# Bordnetzwandler.net
KiCad netlist of a schematic drawn in EAGLE
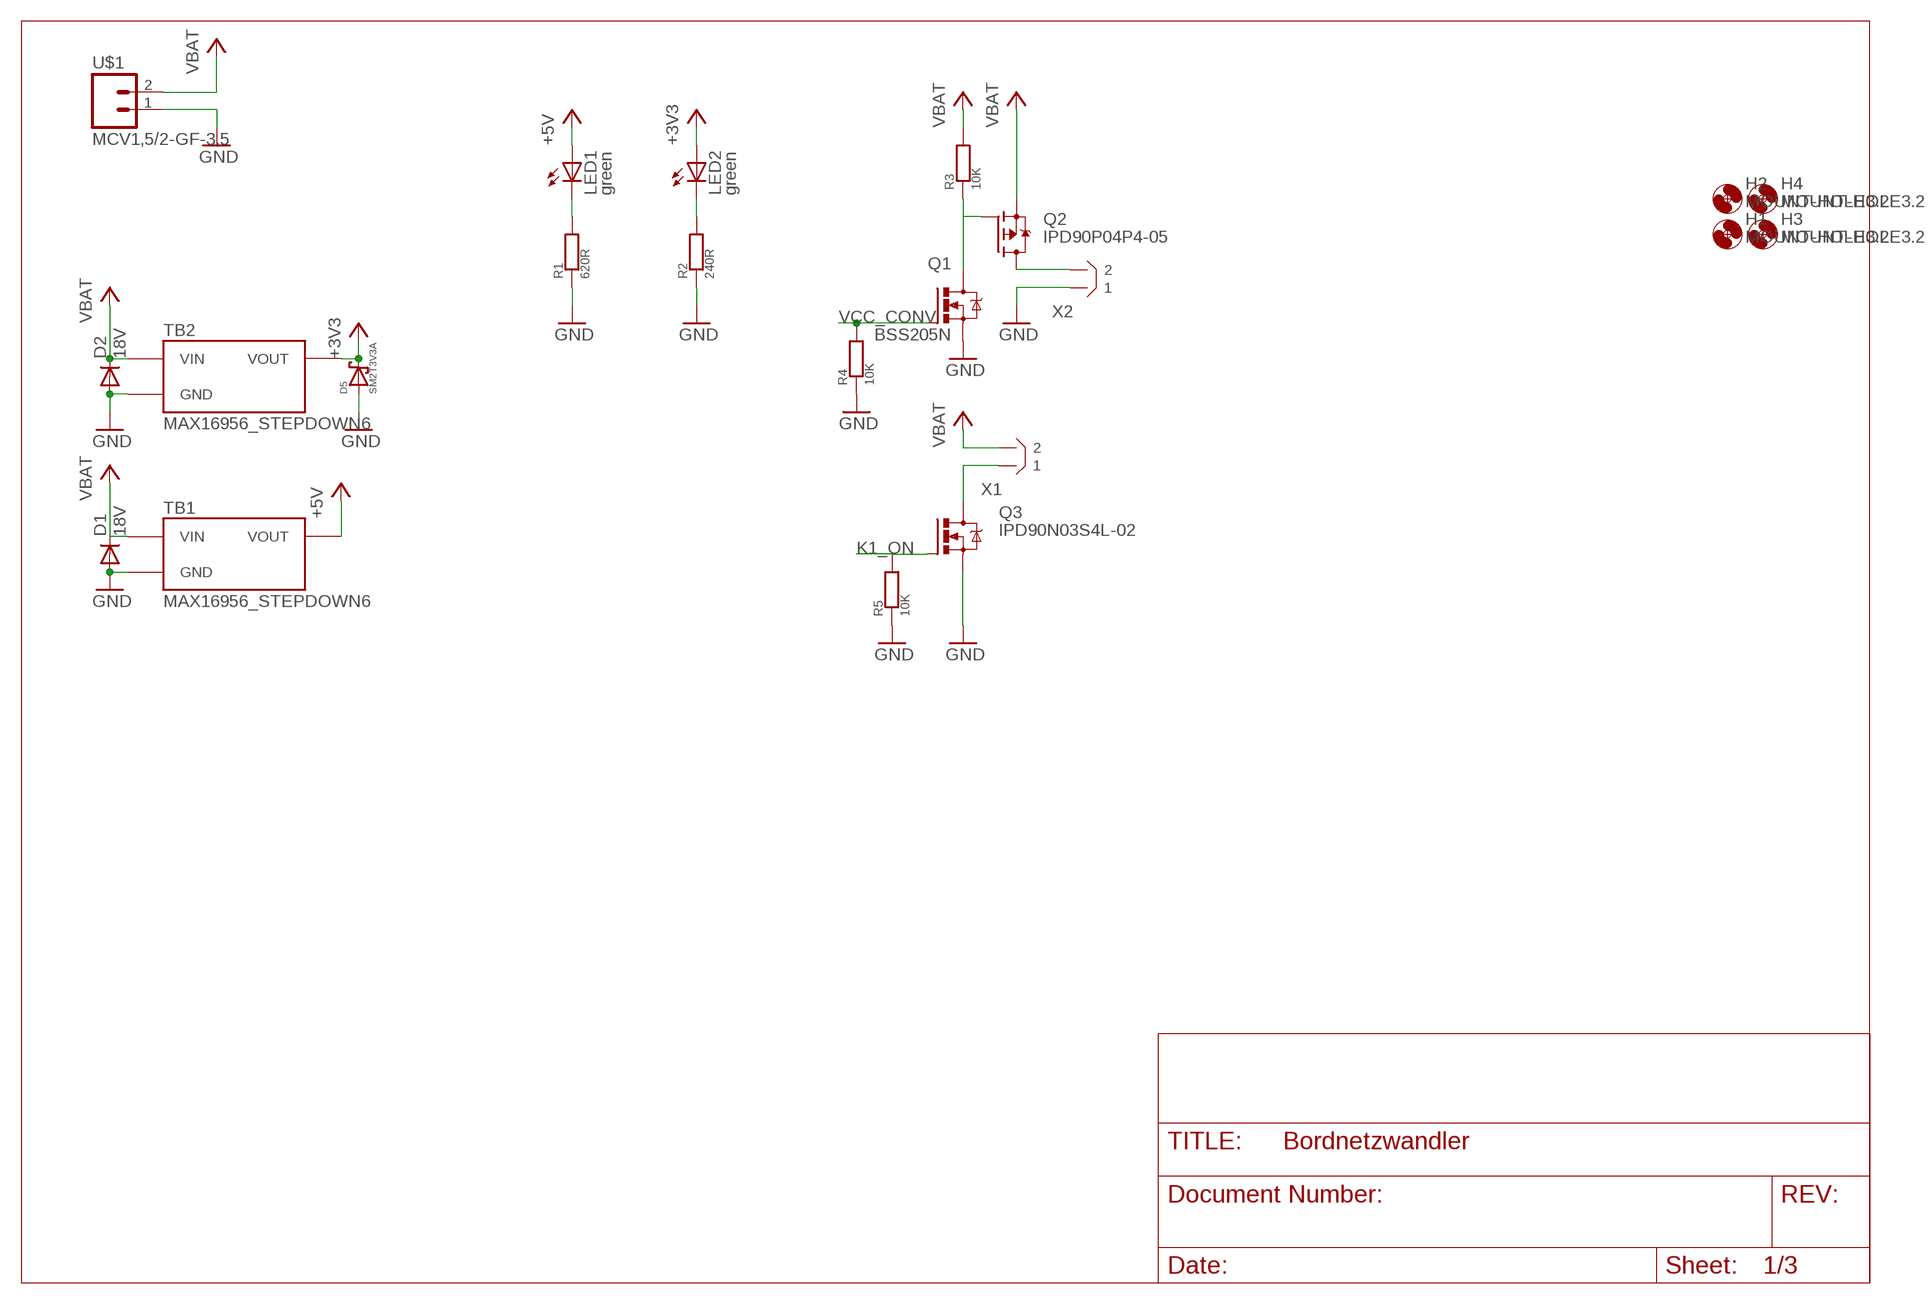
[diagram p0: schematic, sheet 1]
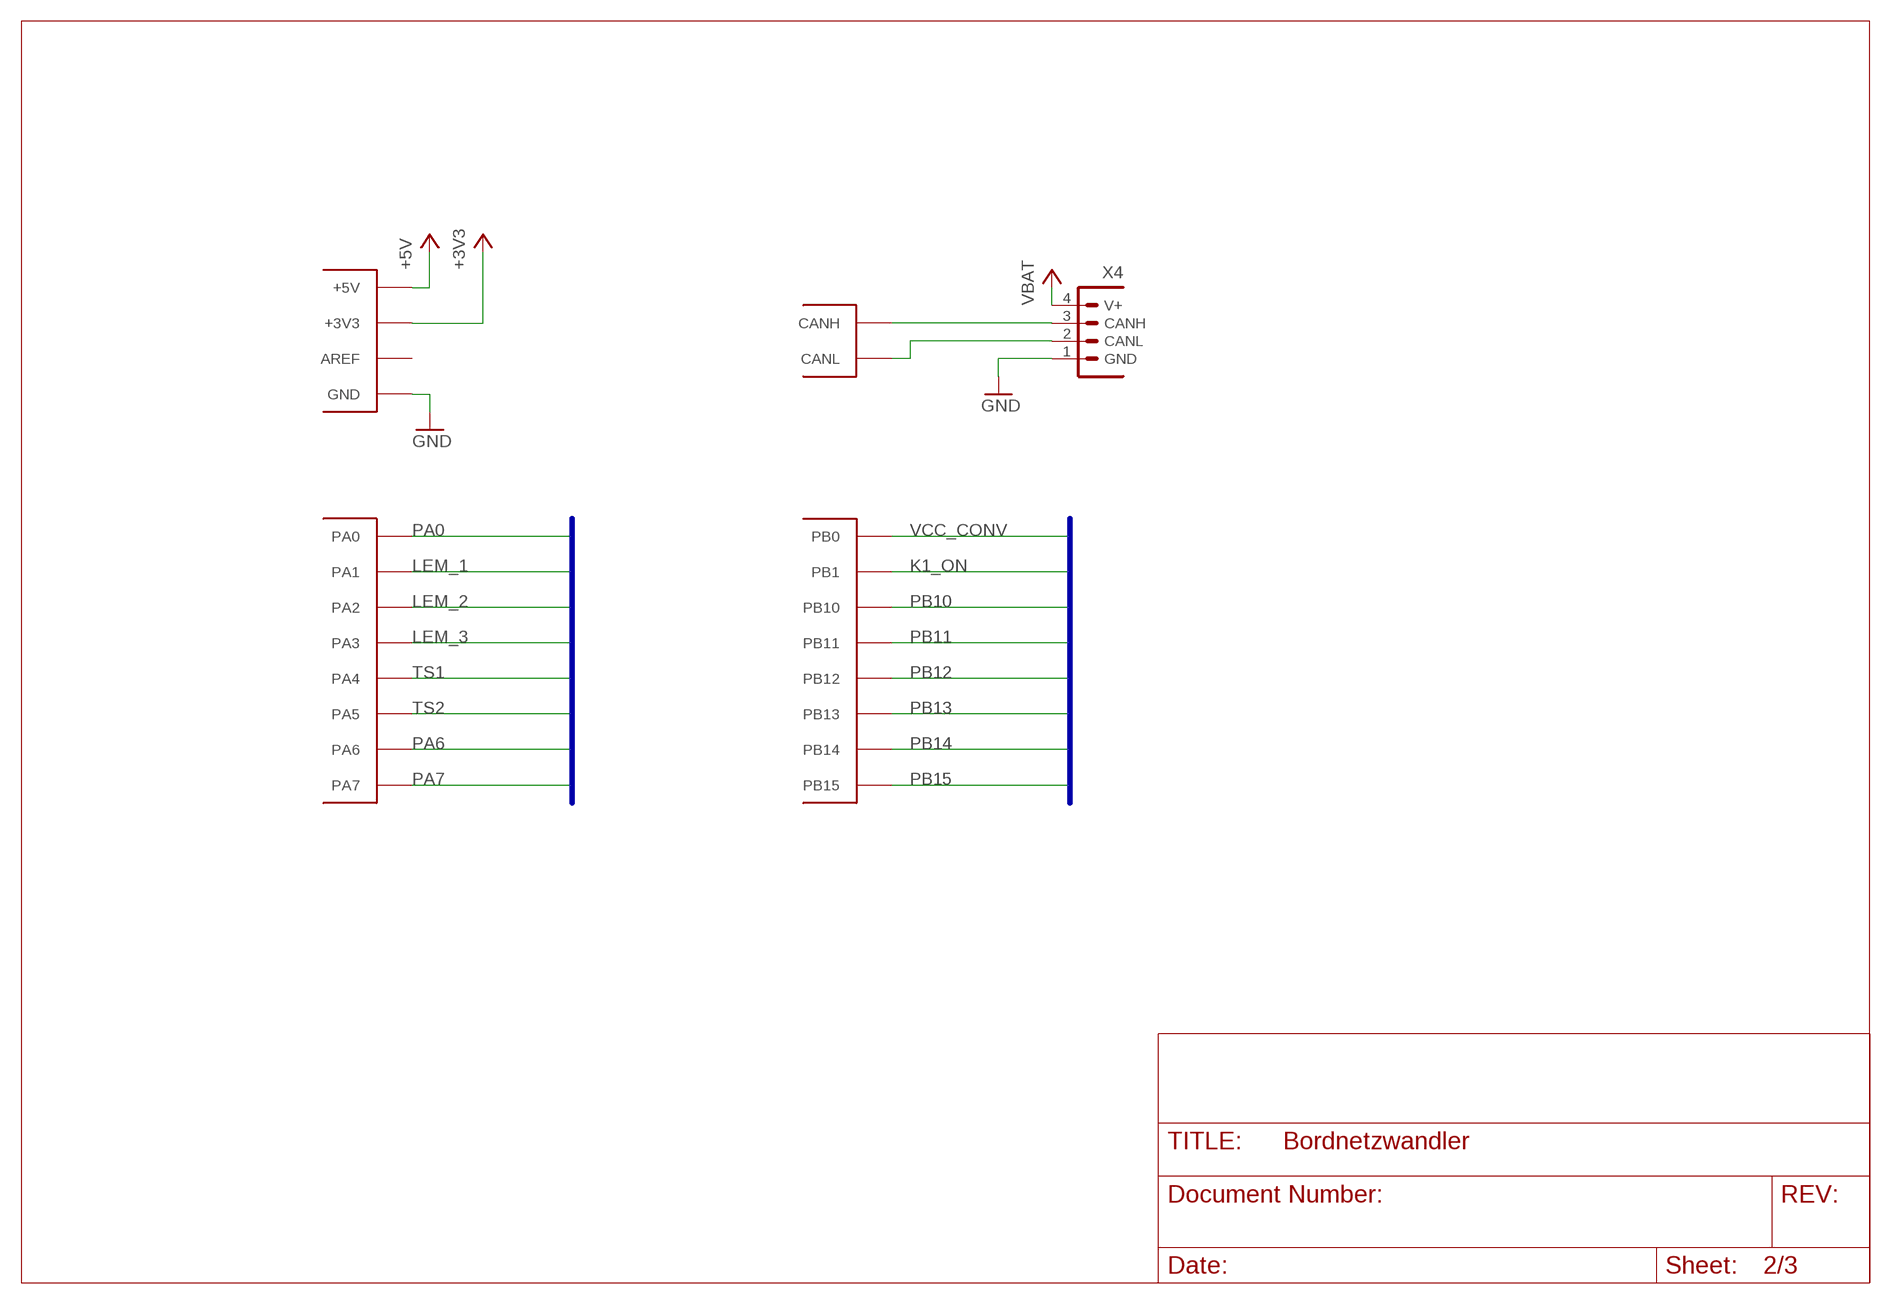
[diagram p1: schematic, sheet 2]
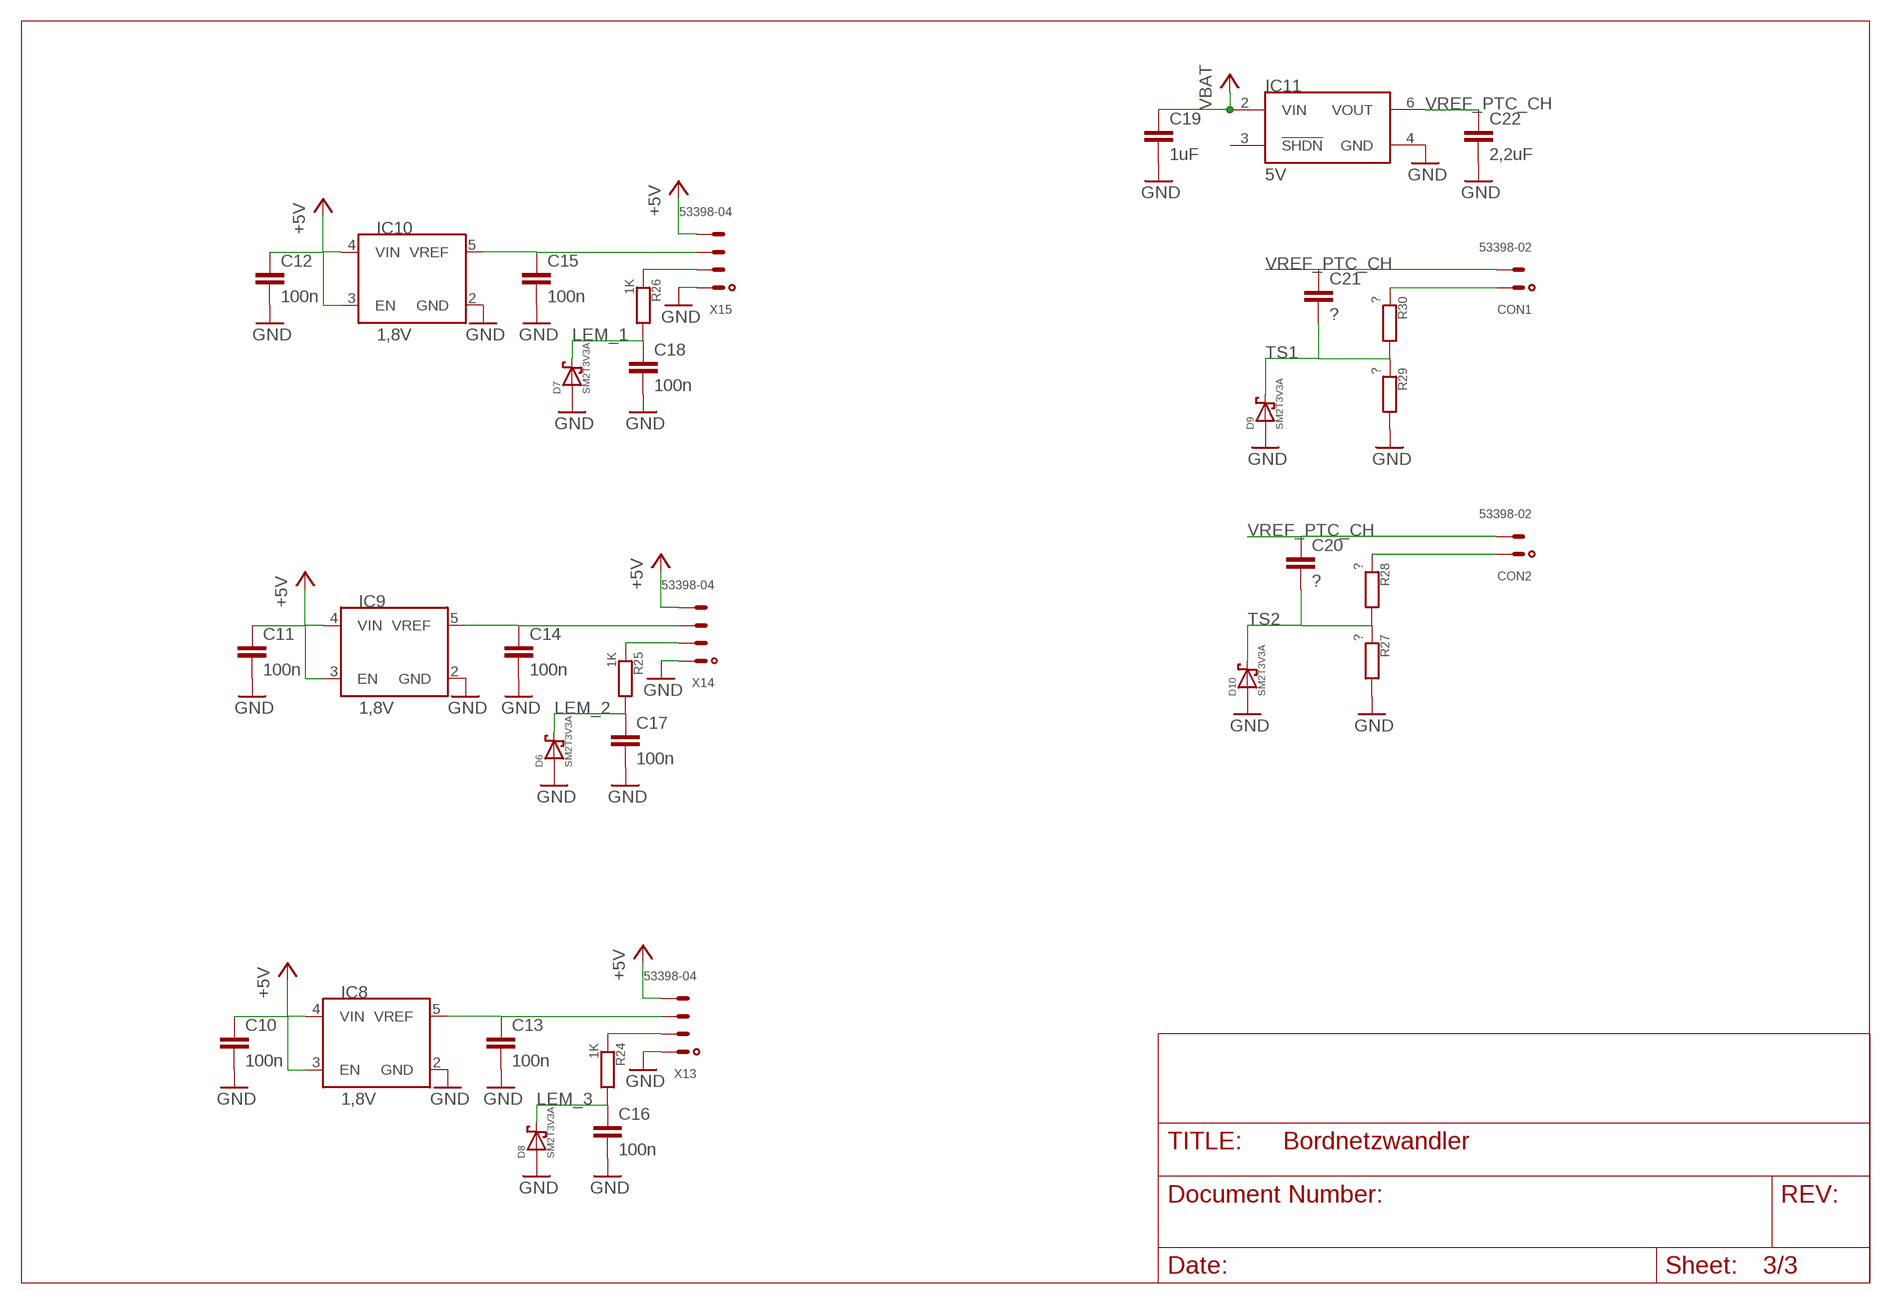
[diagram p2: schematic, sheet 3]

(export (version "E")
  (design (tool "Eeschema 10.0.6"))
  (components
    (comp (ref "CANIO_1")
      (value "STM32F103XX_CAN-IO-EXPANDER")
      (footprint "eagle-import:STM32F103XX_CANIO-EXPANDER")
      (libsource (lib "eagle-import") (part "STM32F103XX_CAN-IO-EXPANDER"))
    )
    (comp (ref "X4")
      (value "CIOC_4-1-FV-A_CAN-BELEGUNG")
      (footprint "eagle-import:CIOC_4-1-FV")
      (libsource (lib "eagle-import") (part "CIOC_4-1-FV-A_CAN-BELEGUNG"))
    )
    (comp (ref "C10")
      (value "100n")
      (footprint "eagle-import:C0805")
      (libsource (lib "eagle-import") (part "C-EUC0805"))
    )
    (comp (ref "C11")
      (value "100n")
      (footprint "eagle-import:C0805")
      (libsource (lib "eagle-import") (part "C-EUC0805"))
    )
    (comp (ref "C12")
      (value "100n")
      (footprint "eagle-import:C0805")
      (libsource (lib "eagle-import") (part "C-EUC0805"))
    )
    (comp (ref "C13")
      (value "100n")
      (footprint "eagle-import:C0805")
      (libsource (lib "eagle-import") (part "C-EUC0805"))
    )
    (comp (ref "C14")
      (value "100n")
      (footprint "eagle-import:C0805")
      (libsource (lib "eagle-import") (part "C-EUC0805"))
    )
    (comp (ref "C15")
      (value "100n")
      (footprint "eagle-import:C0805")
      (libsource (lib "eagle-import") (part "C-EUC0805"))
    )
    (comp (ref "C16")
      (value "100n")
      (footprint "eagle-import:C0805")
      (libsource (lib "eagle-import") (part "C-EUC0805"))
    )
    (comp (ref "C17")
      (value "100n")
      (footprint "eagle-import:C0805")
      (libsource (lib "eagle-import") (part "C-EUC0805"))
    )
    (comp (ref "C18")
      (value "100n")
      (footprint "eagle-import:C0805")
      (libsource (lib "eagle-import") (part "C-EUC0805"))
    )
    (comp (ref "C19")
      (value "1uF")
      (footprint "eagle-import:C0805")
      (libsource (lib "eagle-import") (part "C-EUC0805"))
    )
    (comp (ref "C20")
      (value "?")
      (footprint "eagle-import:C0805")
      (libsource (lib "eagle-import") (part "C-EUC0805"))
    )
    (comp (ref "C21")
      (value "?")
      (footprint "eagle-import:C0805")
      (libsource (lib "eagle-import") (part "C-EUC0805"))
    )
    (comp (ref "C22")
      (value "2,2uF")
      (footprint "eagle-import:C0805")
      (libsource (lib "eagle-import") (part "C-EUC0805"))
    )
    (comp (ref "CON1")
      (value "53398-02")
      (footprint "eagle-import:53398-02")
      (libsource (lib "eagle-import") (part "53?-02398"))
    )
    (comp (ref "CON2")
      (value "53398-02")
      (footprint "eagle-import:53398-02")
      (libsource (lib "eagle-import") (part "53?-02398"))
    )
    (comp (ref "D6")
      (value "SM2T3V3A")
      (footprint "eagle-import:SM2T3V3A")
      (libsource (lib "eagle-import") (part "SM2T3V3A"))
    )
    (comp (ref "D7")
      (value "SM2T3V3A")
      (footprint "eagle-import:SM2T3V3A")
      (libsource (lib "eagle-import") (part "SM2T3V3A"))
    )
    (comp (ref "D8")
      (value "SM2T3V3A")
      (footprint "eagle-import:SM2T3V3A")
      (libsource (lib "eagle-import") (part "SM2T3V3A"))
    )
    (comp (ref "D9")
      (value "SM2T3V3A")
      (footprint "eagle-import:SM2T3V3A")
      (libsource (lib "eagle-import") (part "SM2T3V3A"))
    )
    (comp (ref "D10")
      (value "SM2T3V3A")
      (footprint "eagle-import:SM2T3V3A")
      (libsource (lib "eagle-import") (part "SM2T3V3A"))
    )
    (comp (ref "IC8")
      (value "1,8V")
      (footprint "eagle-import:SOT23-5L")
      (libsource (lib "eagle-import") (part "LM4132L"))
    )
    (comp (ref "IC9")
      (value "1,8V")
      (footprint "eagle-import:SOT23-5L")
      (libsource (lib "eagle-import") (part "LM4132L"))
    )
    (comp (ref "IC10")
      (value "1,8V")
      (footprint "eagle-import:SOT23-5L")
      (libsource (lib "eagle-import") (part "LM4132L"))
    )
    (comp (ref "IC11")
      (value "5V")
      (footprint "eagle-import:SO08")
      (libsource (lib "eagle-import") (part "LT1461"))
    )
    (comp (ref "R24")
      (value "1K")
      (footprint "eagle-import:R0805")
      (libsource (lib "eagle-import") (part "R"))
    )
    (comp (ref "R25")
      (value "1K")
      (footprint "eagle-import:R0805")
      (libsource (lib "eagle-import") (part "R"))
    )
    (comp (ref "R26")
      (value "1K")
      (footprint "eagle-import:R0805")
      (libsource (lib "eagle-import") (part "R"))
    )
    (comp (ref "R27")
      (value "?")
      (footprint "eagle-import:R0805")
      (libsource (lib "eagle-import") (part "R"))
    )
    (comp (ref "R28")
      (value "?")
      (footprint "eagle-import:R0805")
      (libsource (lib "eagle-import") (part "R"))
    )
    (comp (ref "R29")
      (value "?")
      (footprint "eagle-import:R0805")
      (libsource (lib "eagle-import") (part "R"))
    )
    (comp (ref "R30")
      (value "?")
      (footprint "eagle-import:R0805")
      (libsource (lib "eagle-import") (part "R"))
    )
    (comp (ref "X13")
      (value "53398-04")
      (footprint "eagle-import:53398-04")
      (libsource (lib "eagle-import") (part "53?-04398"))
    )
    (comp (ref "X14")
      (value "53398-04")
      (footprint "eagle-import:53398-04")
      (libsource (lib "eagle-import") (part "53?-04398"))
    )
    (comp (ref "X15")
      (value "53398-04")
      (footprint "eagle-import:53398-04")
      (libsource (lib "eagle-import") (part "53?-04398"))
    )
    (comp (ref "D1")
      (value "18V")
      (footprint "eagle-import:DO214AA")
      (libsource (lib "eagle-import") (part "DIODE-DO214AA"))
    )
    (comp (ref "D2")
      (value "18V")
      (footprint "eagle-import:DO214AA")
      (libsource (lib "eagle-import") (part "DIODE-DO214AA"))
    )
    (comp (ref "D5")
      (value "SM2T3V3A")
      (footprint "eagle-import:SM2T3V3A")
      (libsource (lib "eagle-import") (part "SM2T3V3A"))
    )
    (comp (ref "H1")
      (value "MOUNT-HOLE3.2")
      (footprint "eagle-import:3,2")
      (libsource (lib "eagle-import") (part "MOUNT-HOLE3.2"))
    )
    (comp (ref "H2")
      (value "MOUNT-HOLE3.2")
      (footprint "eagle-import:3,2")
      (libsource (lib "eagle-import") (part "MOUNT-HOLE3.2"))
    )
    (comp (ref "H3")
      (value "MOUNT-HOLE3.2")
      (footprint "eagle-import:3,2")
      (libsource (lib "eagle-import") (part "MOUNT-HOLE3.2"))
    )
    (comp (ref "H4")
      (value "MOUNT-HOLE3.2")
      (footprint "eagle-import:3,2")
      (libsource (lib "eagle-import") (part "MOUNT-HOLE3.2"))
    )
    (comp (ref "LED1")
      (value "green")
      (footprint "eagle-import:CHIP-LED0805")
      (libsource (lib "eagle-import") (part "LEDCHIP-LED0805"))
    )
    (comp (ref "LED2")
      (value "green")
      (footprint "eagle-import:CHIP-LED0805")
      (libsource (lib "eagle-import") (part "LEDCHIP-LED0805"))
    )
    (comp (ref "Q1")
      (value "BSS205N")
      (footprint "eagle-import:SOT23")
      (libsource (lib "eagle-import") (part "BSS205N"))
    )
    (comp (ref "Q2")
      (value "IPD90P04P4-05")
      (footprint "eagle-import:TO252")
      (libsource (lib "eagle-import") (part "IPD90P04P4-05"))
    )
    (comp (ref "Q3")
      (value "IPD90N03S4L-02")
      (footprint "eagle-import:TO252")
      (libsource (lib "eagle-import") (part "IPD90N03S4L-02"))
    )
    (comp (ref "R1")
      (value "620R")
      (footprint "eagle-import:R0805")
      (libsource (lib "eagle-import") (part "R"))
    )
    (comp (ref "R2")
      (value "240R")
      (footprint "eagle-import:R0805")
      (libsource (lib "eagle-import") (part "R"))
    )
    (comp (ref "R3")
      (value "10K")
      (footprint "eagle-import:R0805")
      (libsource (lib "eagle-import") (part "R"))
    )
    (comp (ref "R4")
      (value "10K")
      (footprint "eagle-import:R0805")
      (libsource (lib "eagle-import") (part "R"))
    )
    (comp (ref "R5")
      (value "10K")
      (footprint "eagle-import:R0805")
      (libsource (lib "eagle-import") (part "R"))
    )
    (comp (ref "TB1")
      (value "MAX16956_STEPDOWN6")
      (footprint "eagle-import:MAX16956_STEPDOWN6")
      (libsource (lib "eagle-import") (part "MAX16956_STEPDOWN6"))
    )
    (comp (ref "TB2")
      (value "MAX16956_STEPDOWN6")
      (footprint "eagle-import:MAX16956_STEPDOWN6")
      (libsource (lib "eagle-import") (part "MAX16956_STEPDOWN6"))
    )
    (comp (ref "U$1")
      (value "MCV1,5/2-GF-3,5")
      (footprint "eagle-import:MCV1,5_2-GF-3,5")
      (libsource (lib "eagle-import") (part "MCV1,5/2-GF-3,5"))
    )
    (comp (ref "X1")
      (value "B2B-XH")
      (footprint "eagle-import:B2B-XH")
      (libsource (lib "eagle-import") (part "?2B-XHB"))
    )
    (comp (ref "X2")
      (value "B2B-XH")
      (footprint "eagle-import:B2B-XH")
      (libsource (lib "eagle-import") (part "?2B-XHB"))
    )
  )
  (nets
    (net (code "1") (name "+3V3") (class "Default")
      (node (ref "CANIO_1") (pin "VCC") (pinfunction "+3V3_VCC") (pintype "power_in"))
      (node (ref "D5") (pin "P$2") (pinfunction "P$2_P$2") (pintype "bidirectional"))
      (node (ref "LED2") (pin "A") (pinfunction "A_A") (pintype "passive"))
      (node (ref "TB2") (pin "VOUT") (pinfunction "VOUT_VOUT") (pintype "passive"))
    )
    (net (code "2") (name "+5V") (class "Default")
      (node (ref "C10") (pin "1") (pinfunction "1_1") (pintype "passive"))
      (node (ref "C11") (pin "1") (pinfunction "1_1") (pintype "passive"))
      (node (ref "C12") (pin "1") (pinfunction "1_1") (pintype "passive"))
      (node (ref "CANIO_1") (pin "+5V") (pinfunction "+5V_+5V") (pintype "power_in"))
      (node (ref "IC10") (pin "3") (pinfunction "EN_3") (pintype "bidirectional"))
      (node (ref "IC10") (pin "4") (pinfunction "VIN_4") (pintype "bidirectional"))
      (node (ref "IC8") (pin "3") (pinfunction "EN_3") (pintype "bidirectional"))
      (node (ref "IC8") (pin "4") (pinfunction "VIN_4") (pintype "bidirectional"))
      (node (ref "IC9") (pin "3") (pinfunction "EN_3") (pintype "bidirectional"))
      (node (ref "IC9") (pin "4") (pinfunction "VIN_4") (pintype "bidirectional"))
      (node (ref "LED1") (pin "A") (pinfunction "A_A") (pintype "passive"))
      (node (ref "TB1") (pin "VOUT") (pinfunction "VOUT_VOUT") (pintype "passive"))
      (node (ref "X13") (pin "4") (pinfunction "4_4") (pintype "passive"))
      (node (ref "X14") (pin "4") (pinfunction "4_4") (pintype "passive"))
      (node (ref "X15") (pin "4") (pinfunction "4_4") (pintype "passive"))
    )
    (net (code "3") (name "GND") (class "Default")
      (node (ref "C10") (pin "2") (pinfunction "2_2") (pintype "passive"))
      (node (ref "C11") (pin "2") (pinfunction "2_2") (pintype "passive"))
      (node (ref "C12") (pin "2") (pinfunction "2_2") (pintype "passive"))
      (node (ref "C13") (pin "2") (pinfunction "2_2") (pintype "passive"))
      (node (ref "C14") (pin "2") (pinfunction "2_2") (pintype "passive"))
      (node (ref "C15") (pin "2") (pinfunction "2_2") (pintype "passive"))
      (node (ref "C16") (pin "2") (pinfunction "2_2") (pintype "passive"))
      (node (ref "C17") (pin "2") (pinfunction "2_2") (pintype "passive"))
      (node (ref "C18") (pin "2") (pinfunction "2_2") (pintype "passive"))
      (node (ref "C19") (pin "2") (pinfunction "2_2") (pintype "passive"))
      (node (ref "C22") (pin "2") (pinfunction "2_2") (pintype "passive"))
      (node (ref "CANIO_1") (pin "GND1") (pinfunction "GND_GND1") (pintype "power_in"))
      (node (ref "D1") (pin "A") (pinfunction "A_A") (pintype "passive"))
      (node (ref "D10") (pin "P$1") (pinfunction "P$1_P$1") (pintype "bidirectional"))
      (node (ref "D10") (pin "P$11") (pinfunction "P$1_P$11") (pintype "bidirectional"))
      (node (ref "D2") (pin "A") (pinfunction "A_A") (pintype "passive"))
      (node (ref "D5") (pin "P$1") (pinfunction "P$1_P$1") (pintype "bidirectional"))
      (node (ref "D5") (pin "P$11") (pinfunction "P$1_P$11") (pintype "bidirectional"))
      (node (ref "D6") (pin "P$1") (pinfunction "P$1_P$1") (pintype "bidirectional"))
      (node (ref "D6") (pin "P$11") (pinfunction "P$1_P$11") (pintype "bidirectional"))
      (node (ref "D7") (pin "P$1") (pinfunction "P$1_P$1") (pintype "bidirectional"))
      (node (ref "D7") (pin "P$11") (pinfunction "P$1_P$11") (pintype "bidirectional"))
      (node (ref "D8") (pin "P$1") (pinfunction "P$1_P$1") (pintype "bidirectional"))
      (node (ref "D8") (pin "P$11") (pinfunction "P$1_P$11") (pintype "bidirectional"))
      (node (ref "D9") (pin "P$1") (pinfunction "P$1_P$1") (pintype "bidirectional"))
      (node (ref "D9") (pin "P$11") (pinfunction "P$1_P$11") (pintype "bidirectional"))
      (node (ref "IC10") (pin "2") (pinfunction "GND_2") (pintype "bidirectional"))
      (node (ref "IC11") (pin "4") (pinfunction "GND_4") (pintype "power_in"))
      (node (ref "IC8") (pin "2") (pinfunction "GND_2") (pintype "bidirectional"))
      (node (ref "IC9") (pin "2") (pinfunction "GND_2") (pintype "bidirectional"))
      (node (ref "Q1") (pin "2") (pinfunction "S_2") (pintype "passive"))
      (node (ref "Q3") (pin "3") (pinfunction "S_3") (pintype "passive"))
      (node (ref "R1") (pin "1") (pinfunction "1_1") (pintype "passive"))
      (node (ref "R2") (pin "1") (pinfunction "1_1") (pintype "passive"))
      (node (ref "R27") (pin "2") (pinfunction "2_2") (pintype "passive"))
      (node (ref "R29") (pin "2") (pinfunction "2_2") (pintype "passive"))
      (node (ref "R4") (pin "1") (pinfunction "1_1") (pintype "passive"))
      (node (ref "R5") (pin "1") (pinfunction "1_1") (pintype "passive"))
      (node (ref "TB1") (pin "GND") (pinfunction "GND_GND") (pintype "power_in"))
      (node (ref "TB1") (pin "GND2") (pinfunction "GND_GND2") (pintype "power_in"))
      (node (ref "TB2") (pin "GND") (pinfunction "GND_GND") (pintype "power_in"))
      (node (ref "TB2") (pin "GND2") (pinfunction "GND_GND2") (pintype "power_in"))
      (node (ref "U$1") (pin "1") (pinfunction "1_1") (pintype "passive"))
      (node (ref "X13") (pin "1") (pinfunction "1_1") (pintype "passive"))
      (node (ref "X14") (pin "1") (pinfunction "1_1") (pintype "passive"))
      (node (ref "X15") (pin "1") (pinfunction "1_1") (pintype "passive"))
      (node (ref "X2") (pin "P$1") (pinfunction "1_P$1") (pintype "bidirectional"))
      (node (ref "X4") (pin "1") (pinfunction "GND_1") (pintype "passive"))
    )
    (net (code "4") (name "K1_ON") (class "Default")
      (node (ref "CANIO_1") (pin "PB1") (pinfunction "PB1_PB1") (pintype "bidirectional"))
      (node (ref "Q3") (pin "1") (pinfunction "G_1") (pintype "passive"))
      (node (ref "R5") (pin "2") (pinfunction "2_2") (pintype "passive"))
    )
    (net (code "5") (name "LEM_1") (class "Default")
      (node (ref "C18") (pin "1") (pinfunction "1_1") (pintype "passive"))
      (node (ref "CANIO_1") (pin "PA1") (pinfunction "PA1_PA1") (pintype "bidirectional"))
      (node (ref "D7") (pin "P$2") (pinfunction "P$2_P$2") (pintype "bidirectional"))
      (node (ref "R26") (pin "2") (pinfunction "2_2") (pintype "passive"))
    )
    (net (code "6") (name "LEM_2") (class "Default")
      (node (ref "C17") (pin "1") (pinfunction "1_1") (pintype "passive"))
      (node (ref "CANIO_1") (pin "PA2") (pinfunction "PA2_PA2") (pintype "bidirectional"))
      (node (ref "D6") (pin "P$2") (pinfunction "P$2_P$2") (pintype "bidirectional"))
      (node (ref "R25") (pin "2") (pinfunction "2_2") (pintype "passive"))
    )
    (net (code "7") (name "LEM_3") (class "Default")
      (node (ref "C16") (pin "1") (pinfunction "1_1") (pintype "passive"))
      (node (ref "CANIO_1") (pin "PA3") (pinfunction "PA3_PA3") (pintype "bidirectional"))
      (node (ref "D8") (pin "P$2") (pinfunction "P$2_P$2") (pintype "bidirectional"))
      (node (ref "R24") (pin "2") (pinfunction "2_2") (pintype "passive"))
    )
    (net (code "8") (name "Net-(CON1-Pad1)") (class "Default")
      (node (ref "CON1") (pin "1") (pinfunction "1_1") (pintype "passive"))
      (node (ref "R30") (pin "1") (pinfunction "1_1") (pintype "passive"))
    )
    (net (code "9") (name "Net-(CON2-Pad1)") (class "Default")
      (node (ref "CON2") (pin "1") (pinfunction "1_1") (pintype "passive"))
      (node (ref "R28") (pin "1") (pinfunction "1_1") (pintype "passive"))
    )
    (net (code "10") (name "Net-(IC8-VREF)") (class "Default")
      (node (ref "C13") (pin "1") (pinfunction "1_1") (pintype "passive"))
      (node (ref "IC8") (pin "5") (pinfunction "VREF_5") (pintype "bidirectional"))
      (node (ref "X13") (pin "3") (pinfunction "3_3") (pintype "passive"))
    )
    (net (code "11") (name "Net-(IC9-VREF)") (class "Default")
      (node (ref "C14") (pin "1") (pinfunction "1_1") (pintype "passive"))
      (node (ref "IC9") (pin "5") (pinfunction "VREF_5") (pintype "bidirectional"))
      (node (ref "X14") (pin "3") (pinfunction "3_3") (pintype "passive"))
    )
    (net (code "12") (name "Net-(IC10-VREF)") (class "Default")
      (node (ref "C15") (pin "1") (pinfunction "1_1") (pintype "passive"))
      (node (ref "IC10") (pin "5") (pinfunction "VREF_5") (pintype "bidirectional"))
      (node (ref "X15") (pin "3") (pinfunction "3_3") (pintype "passive"))
    )
    (net (code "13") (name "Net-(LED1-PadC)") (class "Default")
      (node (ref "LED1") (pin "C") (pinfunction "C_C") (pintype "passive"))
      (node (ref "R1") (pin "2") (pinfunction "2_2") (pintype "passive"))
    )
    (net (code "14") (name "Net-(LED2-PadC)") (class "Default")
      (node (ref "LED2") (pin "C") (pinfunction "C_C") (pintype "passive"))
      (node (ref "R2") (pin "2") (pinfunction "2_2") (pintype "passive"))
    )
    (net (code "15") (name "Net-(Q1-D)") (class "Default")
      (node (ref "Q1") (pin "3") (pinfunction "D_3") (pintype "passive"))
      (node (ref "Q2") (pin "1") (pinfunction "G_1") (pintype "passive"))
      (node (ref "R3") (pin "1") (pinfunction "1_1") (pintype "passive"))
    )
    (net (code "16") (name "Net-(Q2-D)") (class "Default")
      (node (ref "Q2") (pin "2") (pinfunction "D_2") (pintype "passive"))
      (node (ref "X2") (pin "P$2") (pinfunction "2_P$2") (pintype "bidirectional"))
    )
    (net (code "17") (name "Net-(Q3-D)") (class "Default")
      (node (ref "Q3") (pin "2") (pinfunction "D_2") (pintype "passive"))
      (node (ref "X1") (pin "P$1") (pinfunction "1_P$1") (pintype "bidirectional"))
    )
    (net (code "18") (name "Net-(R24-Pad1)") (class "Default")
      (node (ref "R24") (pin "1") (pinfunction "1_1") (pintype "passive"))
      (node (ref "X13") (pin "2") (pinfunction "2_2") (pintype "passive"))
    )
    (net (code "19") (name "Net-(R25-Pad1)") (class "Default")
      (node (ref "R25") (pin "1") (pinfunction "1_1") (pintype "passive"))
      (node (ref "X14") (pin "2") (pinfunction "2_2") (pintype "passive"))
    )
    (net (code "20") (name "Net-(R26-Pad1)") (class "Default")
      (node (ref "R26") (pin "1") (pinfunction "1_1") (pintype "passive"))
      (node (ref "X15") (pin "2") (pinfunction "2_2") (pintype "passive"))
    )
    (net (code "21") (name "Net-(X4-CANH)") (class "Default")
      (node (ref "CANIO_1") (pin "CANH") (pinfunction "CANH_CANH") (pintype "bidirectional"))
      (node (ref "X4") (pin "3") (pinfunction "CANH_3") (pintype "passive"))
    )
    (net (code "22") (name "Net-(X4-CANL)") (class "Default")
      (node (ref "CANIO_1") (pin "CANL") (pinfunction "CANL_CANL") (pintype "bidirectional"))
      (node (ref "X4") (pin "2") (pinfunction "CANL_2") (pintype "passive"))
    )
    (net (code "23") (name "PA0") (class "Default")
      (node (ref "CANIO_1") (pin "PA0") (pinfunction "PA0_PA0") (pintype "bidirectional"))
    )
    (net (code "24") (name "PA6") (class "Default")
      (node (ref "CANIO_1") (pin "PA6") (pinfunction "PA6_PA6") (pintype "bidirectional"))
    )
    (net (code "25") (name "PA7") (class "Default")
      (node (ref "CANIO_1") (pin "PA7") (pinfunction "PA7_PA7") (pintype "bidirectional"))
    )
    (net (code "26") (name "PB10") (class "Default")
      (node (ref "CANIO_1") (pin "PB10") (pinfunction "PB10_PB10") (pintype "bidirectional"))
    )
    (net (code "27") (name "PB11") (class "Default")
      (node (ref "CANIO_1") (pin "PB11") (pinfunction "PB11_PB11") (pintype "bidirectional"))
    )
    (net (code "28") (name "PB12") (class "Default")
      (node (ref "CANIO_1") (pin "PB12") (pinfunction "PB12_PB12") (pintype "bidirectional"))
    )
    (net (code "29") (name "PB13") (class "Default")
      (node (ref "CANIO_1") (pin "PB13") (pinfunction "PB13_PB13") (pintype "bidirectional"))
    )
    (net (code "30") (name "PB14") (class "Default")
      (node (ref "CANIO_1") (pin "PB14") (pinfunction "PB14_PB14") (pintype "bidirectional"))
    )
    (net (code "31") (name "PB15") (class "Default")
      (node (ref "CANIO_1") (pin "PB15") (pinfunction "PB15_PB15") (pintype "bidirectional"))
    )
    (net (code "32") (name "TS1") (class "Default")
      (node (ref "C21") (pin "2") (pinfunction "2_2") (pintype "passive"))
      (node (ref "CANIO_1") (pin "PA4") (pinfunction "PA4_PA4") (pintype "bidirectional"))
      (node (ref "D9") (pin "P$2") (pinfunction "P$2_P$2") (pintype "bidirectional"))
      (node (ref "R29") (pin "1") (pinfunction "1_1") (pintype "passive"))
      (node (ref "R30") (pin "2") (pinfunction "2_2") (pintype "passive"))
    )
    (net (code "33") (name "TS2") (class "Default")
      (node (ref "C20") (pin "2") (pinfunction "2_2") (pintype "passive"))
      (node (ref "CANIO_1") (pin "PA5") (pinfunction "PA5_PA5") (pintype "bidirectional"))
      (node (ref "D10") (pin "P$2") (pinfunction "P$2_P$2") (pintype "bidirectional"))
      (node (ref "R27") (pin "1") (pinfunction "1_1") (pintype "passive"))
      (node (ref "R28") (pin "2") (pinfunction "2_2") (pintype "passive"))
    )
    (net (code "34") (name "VBAT") (class "Default")
      (node (ref "C19") (pin "1") (pinfunction "1_1") (pintype "passive"))
      (node (ref "D1") (pin "C") (pinfunction "C_C") (pintype "passive"))
      (node (ref "D2") (pin "C") (pinfunction "C_C") (pintype "passive"))
      (node (ref "IC11") (pin "2") (pinfunction "VIN_2") (pintype "passive"))
      (node (ref "Q2") (pin "3") (pinfunction "S_3") (pintype "passive"))
      (node (ref "R3") (pin "2") (pinfunction "2_2") (pintype "passive"))
      (node (ref "TB1") (pin "VIN") (pinfunction "VIN_VIN") (pintype "passive"))
      (node (ref "TB2") (pin "VIN") (pinfunction "VIN_VIN") (pintype "passive"))
      (node (ref "U$1") (pin "2") (pinfunction "2_2") (pintype "passive"))
      (node (ref "X1") (pin "P$2") (pinfunction "2_P$2") (pintype "bidirectional"))
      (node (ref "X4") (pin "4") (pinfunction "V+_4") (pintype "passive"))
    )
    (net (code "35") (name "VCC_CONV") (class "Default")
      (node (ref "CANIO_1") (pin "PB0") (pinfunction "PB0_PB0") (pintype "bidirectional"))
      (node (ref "Q1") (pin "1") (pinfunction "G_1") (pintype "passive"))
      (node (ref "R4") (pin "2") (pinfunction "2_2") (pintype "passive"))
    )
    (net (code "36") (name "VREF_PTC_CH") (class "Default")
      (node (ref "C20") (pin "1") (pinfunction "1_1") (pintype "passive"))
      (node (ref "C21") (pin "1") (pinfunction "1_1") (pintype "passive"))
      (node (ref "C22") (pin "1") (pinfunction "1_1") (pintype "passive"))
      (node (ref "CON1") (pin "2") (pinfunction "2_2") (pintype "passive"))
      (node (ref "CON2") (pin "2") (pinfunction "2_2") (pintype "passive"))
      (node (ref "IC11") (pin "6") (pinfunction "VOUT_6") (pintype "bidirectional"))
    )
    (net (code "37") (name "unconnected-(CANIO_1-PadAREF)") (class "Default")
      (node (ref "CANIO_1") (pin "AREF") (pinfunction "AREF_AREF") (pintype "output"))
    )
    (net (code "38") (name "unconnected-(IC11-~{SHDN}-Pad3)") (class "Default")
      (node (ref "IC11") (pin "3") (pinfunction "~{SHDN}_3") (pintype "passive"))
    )
  )
)
